# LSM9DS0-breakout.net
KiCad netlist of a schematic drawn in EAGLE
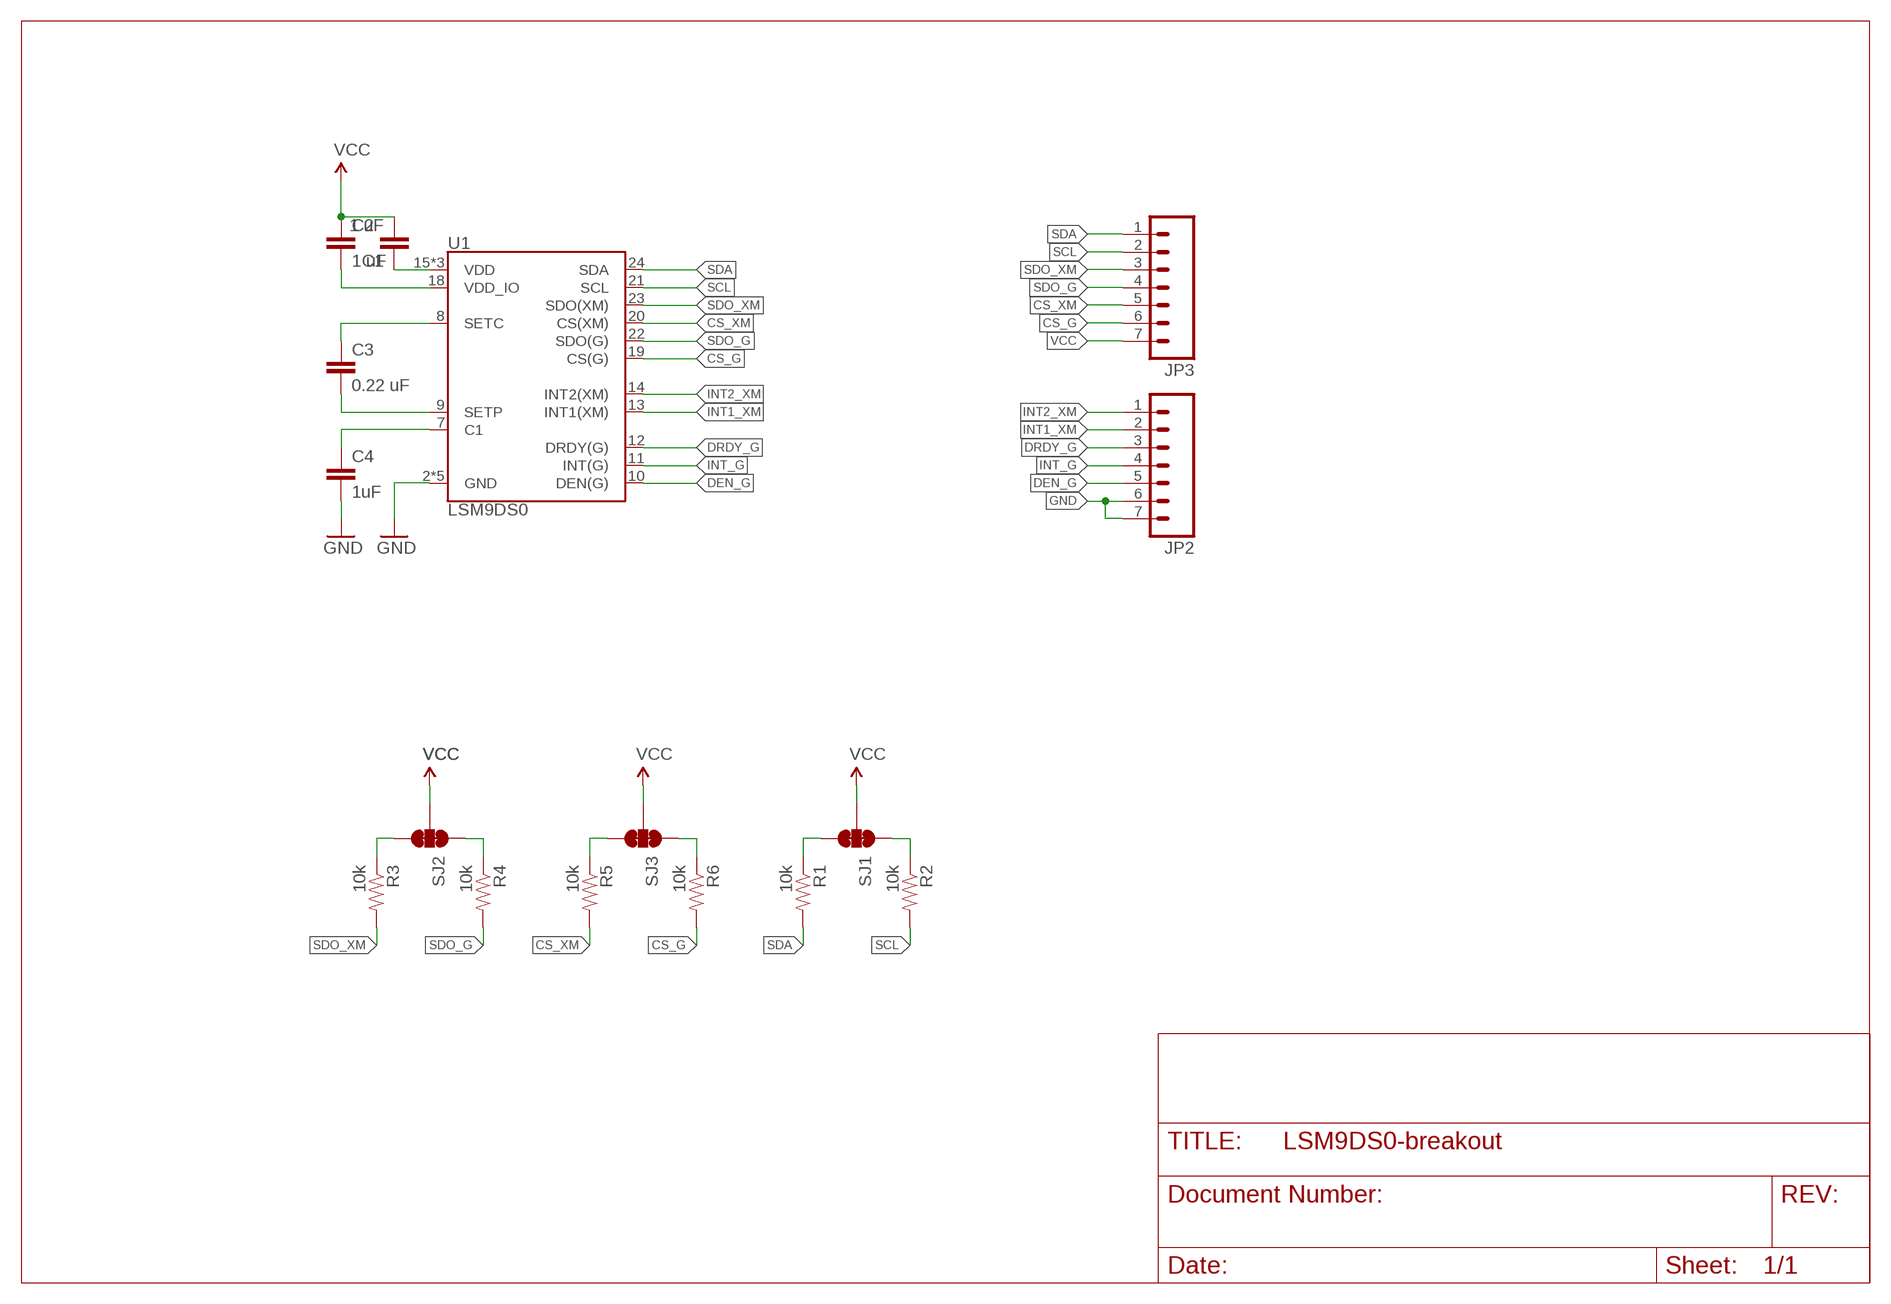
[diagram p0: schematic, sheet 1]

(export (version "E")
  (design (tool "Eeschema 10.0.6"))
  (components
    (comp (ref "C1")
      (value "1 uF")
      (footprint "eagle-import:0603-CAP")
      (libsource (lib "eagle-import") (part "CAP0603-CAP"))
    )
    (comp (ref "C2")
      (value "1 uF")
      (footprint "eagle-import:0603-CAP")
      (libsource (lib "eagle-import") (part "CAP0603-CAP"))
    )
    (comp (ref "C3")
      (value "0.22 uF")
      (footprint "eagle-import:0603-CAP")
      (libsource (lib "eagle-import") (part "CAP0603-CAP"))
    )
    (comp (ref "C4")
      (value "1uF")
      (footprint "eagle-import:0603-CAP")
      (libsource (lib "eagle-import") (part "CAP0603-CAP"))
    )
    (comp (ref "JP2")
      (value "M07")
      (footprint "eagle-import:1X07")
      (libsource (lib "eagle-import") (part "M07"))
    )
    (comp (ref "JP3")
      (value "M07")
      (footprint "eagle-import:1X07")
      (libsource (lib "eagle-import") (part "M07"))
    )
    (comp (ref "R1")
      (value "10k")
      (footprint "eagle-import:0603-RES")
      (libsource (lib "eagle-import") (part "RESISTOR0603-RES"))
    )
    (comp (ref "R2")
      (value "10k")
      (footprint "eagle-import:0603-RES")
      (libsource (lib "eagle-import") (part "RESISTOR0603-RES"))
    )
    (comp (ref "R3")
      (value "10k")
      (footprint "eagle-import:0603-RES")
      (libsource (lib "eagle-import") (part "RESISTOR0603-RES"))
    )
    (comp (ref "R4")
      (value "10k")
      (footprint "eagle-import:0603-RES")
      (libsource (lib "eagle-import") (part "RESISTOR0603-RES"))
    )
    (comp (ref "R5")
      (value "10k")
      (footprint "eagle-import:0603-RES")
      (libsource (lib "eagle-import") (part "RESISTOR0603-RES"))
    )
    (comp (ref "R6")
      (value "10k")
      (footprint "eagle-import:0603-RES")
      (libsource (lib "eagle-import") (part "RESISTOR0603-RES"))
    )
    (comp (ref "SJ1")
      (value "JUMPER-PAD-3-NC_BY_TRACE")
      (footprint "eagle-import:PAD-JUMPER-3-3OF3_NC_BY_TRACE_YES_SILK_FULL_BOX")
      (libsource (lib "eagle-import") (part "JUMPER-PAD-3-NC_BY_TRACE"))
    )
    (comp (ref "SJ2")
      (value "JUMPER-PAD-3-NC_BY_TRACE")
      (footprint "eagle-import:PAD-JUMPER-3-3OF3_NC_BY_TRACE_YES_SILK_FULL_BOX")
      (libsource (lib "eagle-import") (part "JUMPER-PAD-3-NC_BY_TRACE"))
    )
    (comp (ref "SJ3")
      (value "JUMPER-PAD-3-NC_BY_TRACE")
      (footprint "eagle-import:PAD-JUMPER-3-3OF3_NC_BY_TRACE_YES_SILK_FULL_BOX")
      (libsource (lib "eagle-import") (part "JUMPER-PAD-3-NC_BY_TRACE"))
    )
    (comp (ref "U1")
      (value "LSM9DS0")
      (footprint "eagle-import:LGA-24")
      (libsource (lib "eagle-import") (part "LSM9DS0"))
    )
  )
  (nets
    (net (code "1") (name "CS_G") (class "Default")
      (node (ref "JP3") (pin "6") (pinfunction "6_6") (pintype "passive"))
      (node (ref "R6") (pin "2") (pinfunction "2_2") (pintype "passive"))
      (node (ref "U1") (pin "19") (pinfunction "CS(G)_19") (pintype "bidirectional"))
    )
    (net (code "2") (name "CS_XM") (class "Default")
      (node (ref "JP3") (pin "5") (pinfunction "5_5") (pintype "passive"))
      (node (ref "R5") (pin "2") (pinfunction "2_2") (pintype "passive"))
      (node (ref "U1") (pin "20") (pinfunction "CS(XM)_20") (pintype "bidirectional"))
    )
    (net (code "3") (name "DEN_G") (class "Default")
      (node (ref "JP2") (pin "5") (pinfunction "5_5") (pintype "passive"))
      (node (ref "U1") (pin "10") (pinfunction "DEN(G)_10") (pintype "bidirectional"))
    )
    (net (code "4") (name "DRDY_G") (class "Default")
      (node (ref "JP2") (pin "3") (pinfunction "3_3") (pintype "passive"))
      (node (ref "U1") (pin "12") (pinfunction "DRDY(G)_12") (pintype "bidirectional"))
    )
    (net (code "5") (name "GND") (class "Default")
      (node (ref "C4") (pin "2") (pinfunction "2_2") (pintype "passive"))
      (node (ref "JP2") (pin "6") (pinfunction "6_6") (pintype "passive"))
      (node (ref "JP2") (pin "7") (pinfunction "7_7") (pintype "passive"))
      (node (ref "U1") (pin "2") (pinfunction "GND_2") (pintype "bidirectional"))
      (node (ref "U1") (pin "3") (pinfunction "GND_3") (pintype "bidirectional"))
      (node (ref "U1") (pin "4") (pinfunction "GND_4") (pintype "bidirectional"))
      (node (ref "U1") (pin "5") (pinfunction "GND_5") (pintype "bidirectional"))
      (node (ref "U1") (pin "6") (pinfunction "GND_6") (pintype "bidirectional"))
    )
    (net (code "6") (name "INT1_XM") (class "Default")
      (node (ref "JP2") (pin "2") (pinfunction "2_2") (pintype "passive"))
      (node (ref "U1") (pin "13") (pinfunction "INT1(XM)_13") (pintype "bidirectional"))
    )
    (net (code "7") (name "INT2_XM") (class "Default")
      (node (ref "JP2") (pin "1") (pinfunction "1_1") (pintype "passive"))
      (node (ref "U1") (pin "14") (pinfunction "INT2(XM)_14") (pintype "bidirectional"))
    )
    (net (code "8") (name "INT_G") (class "Default")
      (node (ref "JP2") (pin "4") (pinfunction "4_4") (pintype "passive"))
      (node (ref "U1") (pin "11") (pinfunction "INT(G)_11") (pintype "bidirectional"))
    )
    (net (code "9") (name "Net-(C1-Pad1)") (class "Default")
      (node (ref "C1") (pin "1") (pinfunction "1_1") (pintype "passive"))
      (node (ref "U1") (pin "15") (pinfunction "VDD_15") (pintype "bidirectional"))
      (node (ref "U1") (pin "16") (pinfunction "VDD_16") (pintype "bidirectional"))
      (node (ref "U1") (pin "17") (pinfunction "VDD_17") (pintype "bidirectional"))
    )
    (net (code "10") (name "Net-(R1-Pad1)") (class "Default")
      (node (ref "R1") (pin "1") (pinfunction "1_1") (pintype "passive"))
      (node (ref "SJ1") (pin "3") (pinfunction "3_3") (pintype "passive"))
    )
    (net (code "11") (name "Net-(R2-Pad1)") (class "Default")
      (node (ref "R2") (pin "1") (pinfunction "1_1") (pintype "passive"))
      (node (ref "SJ1") (pin "1") (pinfunction "1_1") (pintype "passive"))
    )
    (net (code "12") (name "Net-(R3-Pad1)") (class "Default")
      (node (ref "R3") (pin "1") (pinfunction "1_1") (pintype "passive"))
      (node (ref "SJ2") (pin "3") (pinfunction "3_3") (pintype "passive"))
    )
    (net (code "13") (name "Net-(R4-Pad1)") (class "Default")
      (node (ref "R4") (pin "1") (pinfunction "1_1") (pintype "passive"))
      (node (ref "SJ2") (pin "1") (pinfunction "1_1") (pintype "passive"))
    )
    (net (code "14") (name "Net-(R5-Pad1)") (class "Default")
      (node (ref "R5") (pin "1") (pinfunction "1_1") (pintype "passive"))
      (node (ref "SJ3") (pin "3") (pinfunction "3_3") (pintype "passive"))
    )
    (net (code "15") (name "Net-(R6-Pad1)") (class "Default")
      (node (ref "R6") (pin "1") (pinfunction "1_1") (pintype "passive"))
      (node (ref "SJ3") (pin "1") (pinfunction "1_1") (pintype "passive"))
    )
    (net (code "16") (name "Net-(U1-C1)") (class "Default")
      (node (ref "C4") (pin "1") (pinfunction "1_1") (pintype "passive"))
      (node (ref "U1") (pin "7") (pinfunction "C1_7") (pintype "bidirectional"))
    )
    (net (code "17") (name "Net-(U1-SETC)") (class "Default")
      (node (ref "C3") (pin "1") (pinfunction "1_1") (pintype "passive"))
      (node (ref "U1") (pin "8") (pinfunction "SETC_8") (pintype "bidirectional"))
    )
    (net (code "18") (name "Net-(U1-SETP)") (class "Default")
      (node (ref "C3") (pin "2") (pinfunction "2_2") (pintype "passive"))
      (node (ref "U1") (pin "9") (pinfunction "SETP_9") (pintype "bidirectional"))
    )
    (net (code "19") (name "Net-(U1-VDD_IO)") (class "Default")
      (node (ref "C2") (pin "2") (pinfunction "2_2") (pintype "passive"))
      (node (ref "U1") (pin "18") (pinfunction "VDD_IO_18") (pintype "bidirectional"))
    )
    (net (code "20") (name "SCL") (class "Default")
      (node (ref "JP3") (pin "2") (pinfunction "2_2") (pintype "passive"))
      (node (ref "R2") (pin "2") (pinfunction "2_2") (pintype "passive"))
      (node (ref "U1") (pin "21") (pinfunction "SCL_21") (pintype "bidirectional"))
    )
    (net (code "21") (name "SDA") (class "Default")
      (node (ref "JP3") (pin "1") (pinfunction "1_1") (pintype "passive"))
      (node (ref "R1") (pin "2") (pinfunction "2_2") (pintype "passive"))
      (node (ref "U1") (pin "24") (pinfunction "SDA_24") (pintype "bidirectional"))
    )
    (net (code "22") (name "SDO_G") (class "Default")
      (node (ref "JP3") (pin "4") (pinfunction "4_4") (pintype "passive"))
      (node (ref "R4") (pin "2") (pinfunction "2_2") (pintype "passive"))
      (node (ref "U1") (pin "22") (pinfunction "SDO(G)_22") (pintype "bidirectional"))
    )
    (net (code "23") (name "SDO_XM") (class "Default")
      (node (ref "JP3") (pin "3") (pinfunction "3_3") (pintype "passive"))
      (node (ref "R3") (pin "2") (pinfunction "2_2") (pintype "passive"))
      (node (ref "U1") (pin "23") (pinfunction "SDO(XM)_23") (pintype "bidirectional"))
    )
    (net (code "24") (name "VCC") (class "Default")
      (node (ref "C1") (pin "2") (pinfunction "2_2") (pintype "passive"))
      (node (ref "C2") (pin "1") (pinfunction "1_1") (pintype "passive"))
      (node (ref "JP3") (pin "7") (pinfunction "7_7") (pintype "passive"))
      (node (ref "SJ1") (pin "2") (pinfunction "2_2") (pintype "passive"))
      (node (ref "SJ2") (pin "2") (pinfunction "2_2") (pintype "passive"))
      (node (ref "SJ3") (pin "2") (pinfunction "2_2") (pintype "passive"))
    )
  )
)
